# 02-multimodal-pmic.net
KiCad netlist of a schematic drawn in Altium Designer
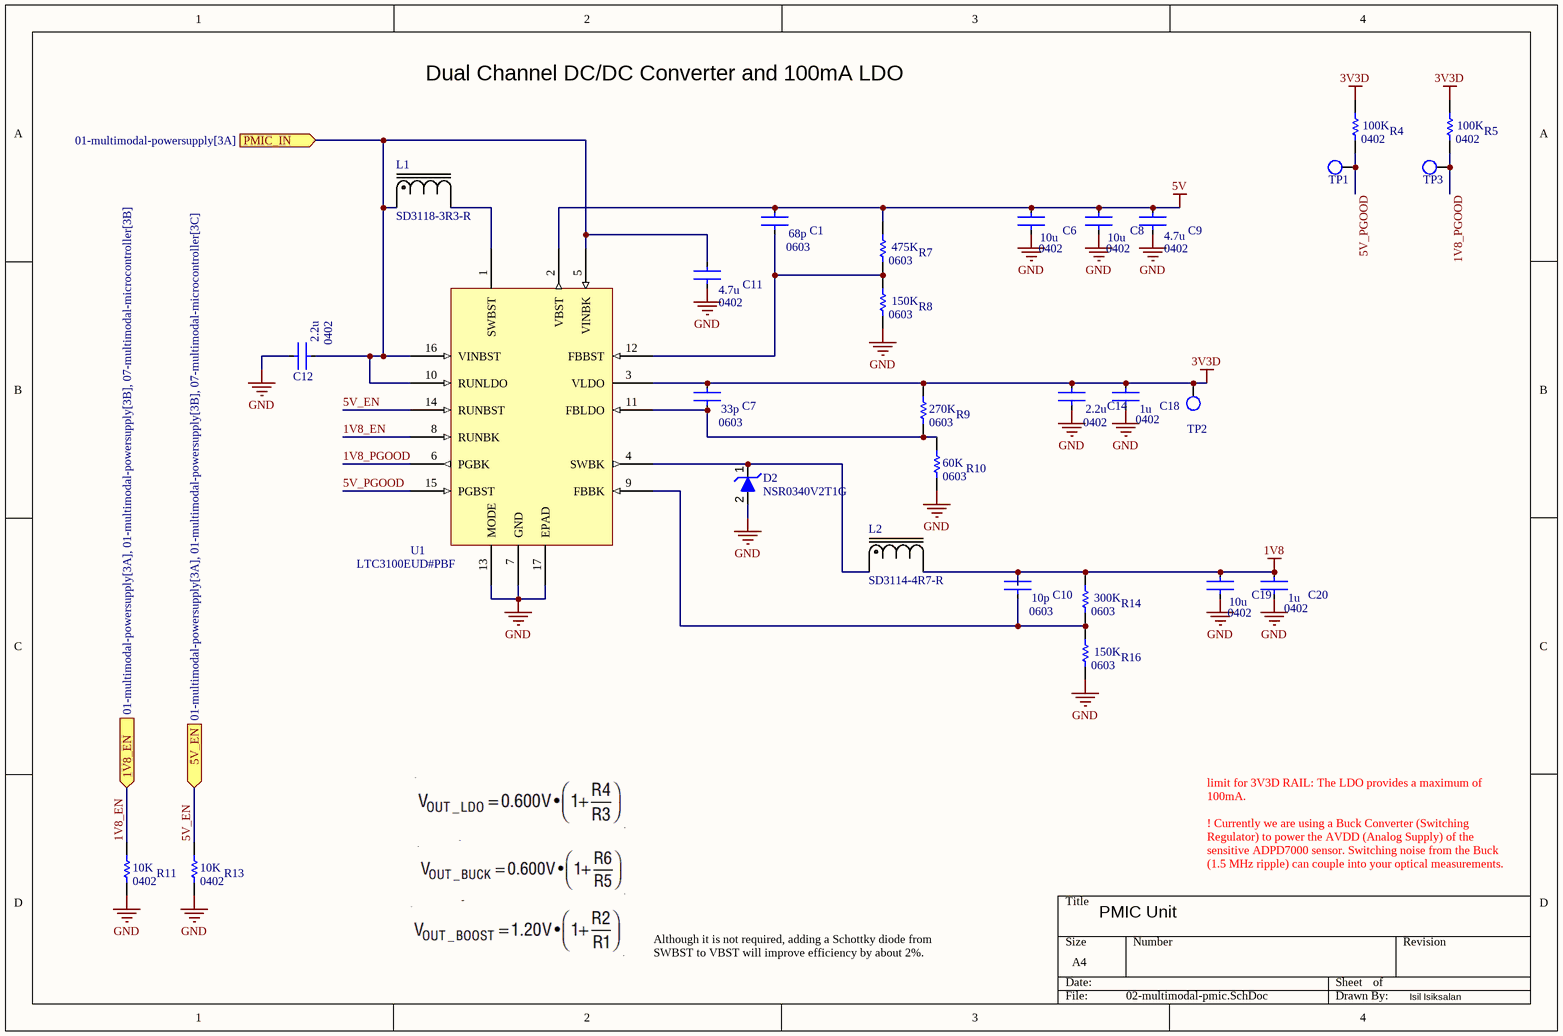
[diagram p0: 02-multimodal-pmic.SchDoc]

(export (version "E")
  (design (tool "Eeschema 10.0.6"))
  (components
    (comp (ref "C1")
      (value "CGA3E2C0G1H680J080AA")
      (footprint "CAPTDK0603")
      (description "CAP CER 68PF 50V C0G 0603")
      (libsource (lib "multimodal") (part "CGA3E2C0G1H680J080AA"))
    )
    (comp (ref "C6")
      (value "GRM155R61A106ME11D")
      (footprint "CAPTDK0402")
      (description "CAP CER 10UF 10V X5R 0402")
      (libsource (lib "multimodal") (part "GRM155R61A106ME11D"))
    )
    (comp (ref "C7")
      (value "CGA3E2C0G1H330J080AA")
      (footprint "CAPTDK0603")
      (description "CAP CER 33PF 50V C0G 0603")
      (libsource (lib "multimodal") (part "CGA3E2C0G1H330J080AA"))
    )
    (comp (ref "C8")
      (value "GRM155R61A106ME11D")
      (footprint "CAPTDK0402")
      (description "CAP CER 10UF 10V X5R 0402")
      (libsource (lib "multimodal") (part "GRM155R61A106ME11D"))
    )
    (comp (ref "C9")
      (value "C1005X5R1A475K050BC")
      (footprint "CAPTDK0402")
      (description "CAP CER 4.7UF 10V X5R 0402")
      (libsource (lib "multimodal") (part "C1005X5R1A475K050BC"))
    )
    (comp (ref "C10")
      (value "CGA3E2C0G1H100D080AA")
      (footprint "CAPTDK0603")
      (description "CAP CER 10PF 50V C0G 0603")
      (libsource (lib "multimodal") (part "CGA3E2C0G1H100D080AA"))
    )
    (comp (ref "C11")
      (value "C1005X5R1A475K050BC")
      (footprint "CAPTDK0402")
      (description "CAP CER 4.7UF 10V X5R 0402")
      (libsource (lib "multimodal") (part "C1005X5R1A475K050BC"))
    )
    (comp (ref "C12")
      (value "CL05A225KO5NQNC")
      (footprint "CAPTDK0402")
      (description "CAP CER 2.2UF 16V X5R 0402")
      (libsource (lib "multimodal") (part "CL05A225KO5NQNC"))
    )
    (comp (ref "C14")
      (value "CL05A225KO5NQNC")
      (footprint "CAPTDK0402")
      (description "CAP CER 2.2UF 16V X5R 0402")
      (libsource (lib "multimodal") (part "CL05A225KO5NQNC"))
    )
    (comp (ref "C18")
      (value "C1005X5R1V105K050BC")
      (footprint "CAPTDK0402")
      (description "CAP CER 1UF 35V X5R 0402")
      (libsource (lib "multimodal") (part "C1005X5R1V105K050BC"))
    )
    (comp (ref "C19")
      (value "GRM155R61A106ME11D")
      (footprint "CAPTDK0402")
      (description "CAP CER 10UF 10V X5R 0402")
      (libsource (lib "multimodal") (part "GRM155R61A106ME11D"))
    )
    (comp (ref "C20")
      (value "C1005X5R1V105K050BC")
      (footprint "CAPTDK0402")
      (description "CAP CER 1UF 35V X5R 0402")
      (libsource (lib "multimodal") (part "C1005X5R1V105K050BC"))
    )
    (comp (ref "D2")
      (value "NSR0340V2T1G")
      (footprint "SOD-523_STM-L")
      (description "DIODE SCHOTTKY 40V 250MA SOD523")
      (fields
        (field (name "MANUFACTURER") "Diodes")
        (field (name "MANUFACTURER PART NUMBER") "DESD3V3S1BL-7B")
      )
      (libsource (lib "multimodal") (part "NSR0340V2T1G"))
    )
    (comp (ref "L1")
      (value "SD3118-3R3-R")
      (footprint "SD3118")
      (description "FIXED IND 3.3UH 1.22A 113 MOHM")
      (fields
        (field (name "MANUFACTURER_PART_NUMBER") "SD3114-4R7-R")
        (field (name "COPYRIGHT") "Copyright (C) 2026 Ultra Librarian. All rights reserved.")
      )
      (libsource (lib "multimodal") (part "SD3118-3R3-R"))
    )
    (comp (ref "L2")
      (value "SD3114-4R7-R")
      (footprint "SD3114")
      (description "No Description Available")
      (fields (field (name "COPYRIGHT") "Copyright (C) 2026 Ultra Librarian. All rights reserved."))
      (libsource (lib "multimodal") (part "SD3114-4R7-R"))
    )
    (comp (ref "R4")
      (value "RMCF0402FT100K")
      (footprint "RES-STACK-POLE-0402")
      (description "RES 100K OHM 1% 1/16W 0402")
      (libsource (lib "multimodal") (part "RMCF0402FT100K"))
    )
    (comp (ref "R5")
      (value "RMCF0402FT100K")
      (footprint "RES-STACK-POLE-0402")
      (description "RES 100K OHM 1% 1/16W 0402")
      (libsource (lib "multimodal") (part "RMCF0402FT100K"))
    )
    (comp (ref "R7")
      (value "RMCF0603FT475K")
      (footprint "RES-STACK-POLE-0603")
      (description "RES 475K OHM 1% 1/10W 0603")
      (libsource (lib "multimodal") (part "RMCF0603FT475K"))
    )
    (comp (ref "R8")
      (value "RC0603FR-07150KL")
      (footprint "RES-STACK-POLE-0603")
      (description "RES 150K OHM 1% 1/10W 0603")
      (libsource (lib "multimodal") (part "RC0603FR-07150KL"))
    )
    (comp (ref "R9")
      (value "RC0603FR-07270KL")
      (footprint "RES-STACK-POLE-0603")
      (description "RES 270K OHM 1% 1/10W 0603")
      (libsource (lib "multimodal") (part "RC0603FR-07270KL"))
    )
    (comp (ref "R10")
      (value "RT0603BRD0760KL")
      (footprint "RES-STACK-POLE-0603")
      (description "RES 60K OHM 0.1% 1/10W 0603")
      (libsource (lib "multimodal") (part "RT0603BRD0760KL"))
    )
    (comp (ref "R11")
      (value "RMCF0402FT10K0")
      (footprint "RES-STACK-POLE-0402")
      (description "RES 10K OHM 1% 1/16W 0402")
      (libsource (lib "multimodal") (part "RMCF0402FT10K0"))
    )
    (comp (ref "R13")
      (value "RMCF0402FT10K0")
      (footprint "RES-STACK-POLE-0402")
      (description "RES 10K OHM 1% 1/16W 0402")
      (libsource (lib "multimodal") (part "RMCF0402FT10K0"))
    )
    (comp (ref "R14")
      (value "RMCF0603FT300K")
      (footprint "RES-STACK-POLE-0603")
      (description "RES 300K OHM 1% 1/10W 0603")
      (libsource (lib "multimodal") (part "RMCF0603FT300K"))
    )
    (comp (ref "R16")
      (value "RC0603FR-07150KL")
      (footprint "RES-STACK-POLE-0603")
      (description "RES 150K OHM 1% 1/10W 0603")
      (libsource (lib "multimodal") (part "RC0603FR-07150KL"))
    )
    (comp (ref "TP1")
      (value "TESTPOINT_S")
      (footprint "TESTPOINT_S")
      (description "Testpoint Surface Pad")
      (libsource (lib "multimodal") (part "TESTPOINT_S"))
    )
    (comp (ref "TP2")
      (value "TESTPOINT_S")
      (footprint "TESTPOINT_S")
      (description "Testpoint Surface Pad")
      (libsource (lib "multimodal") (part "TESTPOINT_S"))
    )
    (comp (ref "TP3")
      (value "TESTPOINT_S")
      (footprint "TESTPOINT_S")
      (description "Testpoint Surface Pad")
      (libsource (lib "multimodal") (part "TESTPOINT_S"))
    )
    (comp (ref "U1")
      (value "LTC3100EUD#PBF")
      (footprint "LTC3100EUD#PBF")
      (fields (field (name "COPYRIGHT") "Copyright (C) 2025 Ultra Librarian. All rights reserved."))
      (libsource (lib "multimodal") (part "LTC3100EUDPBF"))
    )
  )
  (nets
    (net (code "1") (name "/1V8_EN") (class "Default")
      (node (ref "R11") (pin "2") (pinfunction "2_2") (pintype "passive"))
      (node (ref "U1") (pin "8") (pinfunction "RUNBK_8") (pintype "input"))
    )
    (net (code "2") (name "/1V8_PGOOD") (class "Default")
      (node (ref "R5") (pin "1") (pinfunction "1_1") (pintype "passive"))
      (node (ref "TP3") (pin "1") (pinfunction "1_1") (pintype "passive"))
      (node (ref "U1") (pin "6") (pinfunction "PGBK_6") (pintype "output"))
    )
    (net (code "3") (name "/5V_EN") (class "Default")
      (node (ref "R13") (pin "2") (pinfunction "2_2") (pintype "passive"))
      (node (ref "U1") (pin "14") (pinfunction "RUNBST_14") (pintype "input"))
    )
    (net (code "4") (name "/5V_PGOOD") (class "Default")
      (node (ref "R4") (pin "1") (pinfunction "1_1") (pintype "passive"))
      (node (ref "TP1") (pin "1") (pinfunction "1_1") (pintype "passive"))
      (node (ref "U1") (pin "15") (pinfunction "PGBST_15") (pintype "input"))
    )
    (net (code "5") (name "/PMIC_IN") (class "Default")
      (node (ref "C11") (pin "1") (pinfunction "1_1") (pintype "passive"))
      (node (ref "C12") (pin "2") (pinfunction "2_2") (pintype "passive"))
      (node (ref "L1") (pin "1") (pinfunction "1_1") (pintype "passive"))
      (node (ref "U1") (pin "10") (pinfunction "RUNLDO_10") (pintype "input"))
      (node (ref "U1") (pin "16") (pinfunction "VINBST_16") (pintype "input"))
      (node (ref "U1") (pin "5") (pinfunction "VINBK_5") (pintype "input"))
    )
    (net (code "6") (name "1V8") (class "Default")
      (node (ref "C10") (pin "1") (pinfunction "1_1") (pintype "passive"))
      (node (ref "C19") (pin "1") (pinfunction "1_1") (pintype "passive"))
      (node (ref "C20") (pin "1") (pinfunction "1_1") (pintype "passive"))
      (node (ref "L2") (pin "2") (pinfunction "2_2") (pintype "passive"))
      (node (ref "R14") (pin "2") (pinfunction "2_2") (pintype "passive"))
    )
    (net (code "7") (name "3V3D") (class "Default")
      (node (ref "C14") (pin "1") (pinfunction "1_1") (pintype "passive"))
      (node (ref "C18") (pin "1") (pinfunction "1_1") (pintype "passive"))
      (node (ref "C7") (pin "1") (pinfunction "1_1") (pintype "passive"))
      (node (ref "R4") (pin "2") (pinfunction "2_2") (pintype "passive"))
      (node (ref "R5") (pin "2") (pinfunction "2_2") (pintype "passive"))
      (node (ref "R9") (pin "2") (pinfunction "2_2") (pintype "passive"))
      (node (ref "TP2") (pin "1") (pinfunction "1_1") (pintype "passive"))
      (node (ref "U1") (pin "3") (pinfunction "VLDO_3") (pintype "power_in"))
    )
    (net (code "8") (name "5V") (class "Default")
      (node (ref "C1") (pin "1") (pinfunction "1_1") (pintype "passive"))
      (node (ref "C6") (pin "1") (pinfunction "1_1") (pintype "passive"))
      (node (ref "C8") (pin "1") (pinfunction "1_1") (pintype "passive"))
      (node (ref "C9") (pin "1") (pinfunction "1_1") (pintype "passive"))
      (node (ref "R7") (pin "2") (pinfunction "2_2") (pintype "passive"))
      (node (ref "U1") (pin "2") (pinfunction "VBST_2") (pintype "output"))
    )
    (net (code "9") (name "GND") (class "Default")
      (node (ref "C11") (pin "2") (pinfunction "2_2") (pintype "passive"))
      (node (ref "C12") (pin "1") (pinfunction "1_1") (pintype "passive"))
      (node (ref "C14") (pin "2") (pinfunction "2_2") (pintype "passive"))
      (node (ref "C18") (pin "2") (pinfunction "2_2") (pintype "passive"))
      (node (ref "C19") (pin "2") (pinfunction "2_2") (pintype "passive"))
      (node (ref "C20") (pin "2") (pinfunction "2_2") (pintype "passive"))
      (node (ref "C6") (pin "2") (pinfunction "2_2") (pintype "passive"))
      (node (ref "C8") (pin "2") (pinfunction "2_2") (pintype "passive"))
      (node (ref "C9") (pin "2") (pinfunction "2_2") (pintype "passive"))
      (node (ref "D2") (pin "2") (pintype "passive"))
      (node (ref "R10") (pin "1") (pinfunction "1_1") (pintype "passive"))
      (node (ref "R11") (pin "1") (pinfunction "1_1") (pintype "passive"))
      (node (ref "R13") (pin "1") (pinfunction "1_1") (pintype "passive"))
      (node (ref "R16") (pin "1") (pinfunction "1_1") (pintype "passive"))
      (node (ref "R8") (pin "1") (pinfunction "1_1") (pintype "passive"))
      (node (ref "U1") (pin "13") (pinfunction "MODE_13") (pintype "passive"))
      (node (ref "U1") (pin "17") (pinfunction "EPAD_17") (pintype "passive"))
      (node (ref "U1") (pin "7") (pinfunction "GND_7") (pintype "power_in"))
    )
    (net (code "10") (name "Net-(U1-FBBK)") (class "Default")
      (node (ref "C10") (pin "2") (pinfunction "2_2") (pintype "passive"))
      (node (ref "R14") (pin "1") (pinfunction "1_1") (pintype "passive"))
      (node (ref "R16") (pin "2") (pinfunction "2_2") (pintype "passive"))
      (node (ref "U1") (pin "9") (pinfunction "FBBK_9") (pintype "input"))
    )
    (net (code "11") (name "Net-(U1-FBBST)") (class "Default")
      (node (ref "C1") (pin "2") (pinfunction "2_2") (pintype "passive"))
      (node (ref "R7") (pin "1") (pinfunction "1_1") (pintype "passive"))
      (node (ref "R8") (pin "2") (pinfunction "2_2") (pintype "passive"))
      (node (ref "U1") (pin "12") (pinfunction "FBBST_12") (pintype "input"))
    )
    (net (code "12") (name "Net-(U1-FBLDO)") (class "Default")
      (node (ref "C7") (pin "2") (pinfunction "2_2") (pintype "passive"))
      (node (ref "R10") (pin "2") (pinfunction "2_2") (pintype "passive"))
      (node (ref "R9") (pin "1") (pinfunction "1_1") (pintype "passive"))
      (node (ref "U1") (pin "11") (pinfunction "FBLDO_11") (pintype "input"))
    )
    (net (code "13") (name "Net-(U1-SWBK)") (class "Default")
      (node (ref "D2") (pin "1") (pintype "passive"))
      (node (ref "L2") (pin "1") (pinfunction "1_1") (pintype "passive"))
      (node (ref "U1") (pin "4") (pinfunction "SWBK_4") (pintype "output"))
    )
    (net (code "14") (name "Net-(U1-SWBST)") (class "Default")
      (node (ref "L1") (pin "2") (pinfunction "2_2") (pintype "passive"))
      (node (ref "U1") (pin "1") (pinfunction "SWBST_1") (pintype "passive"))
    )
  )
)
